# board.net
KiCad netlist of a schematic drawn in EAGLE
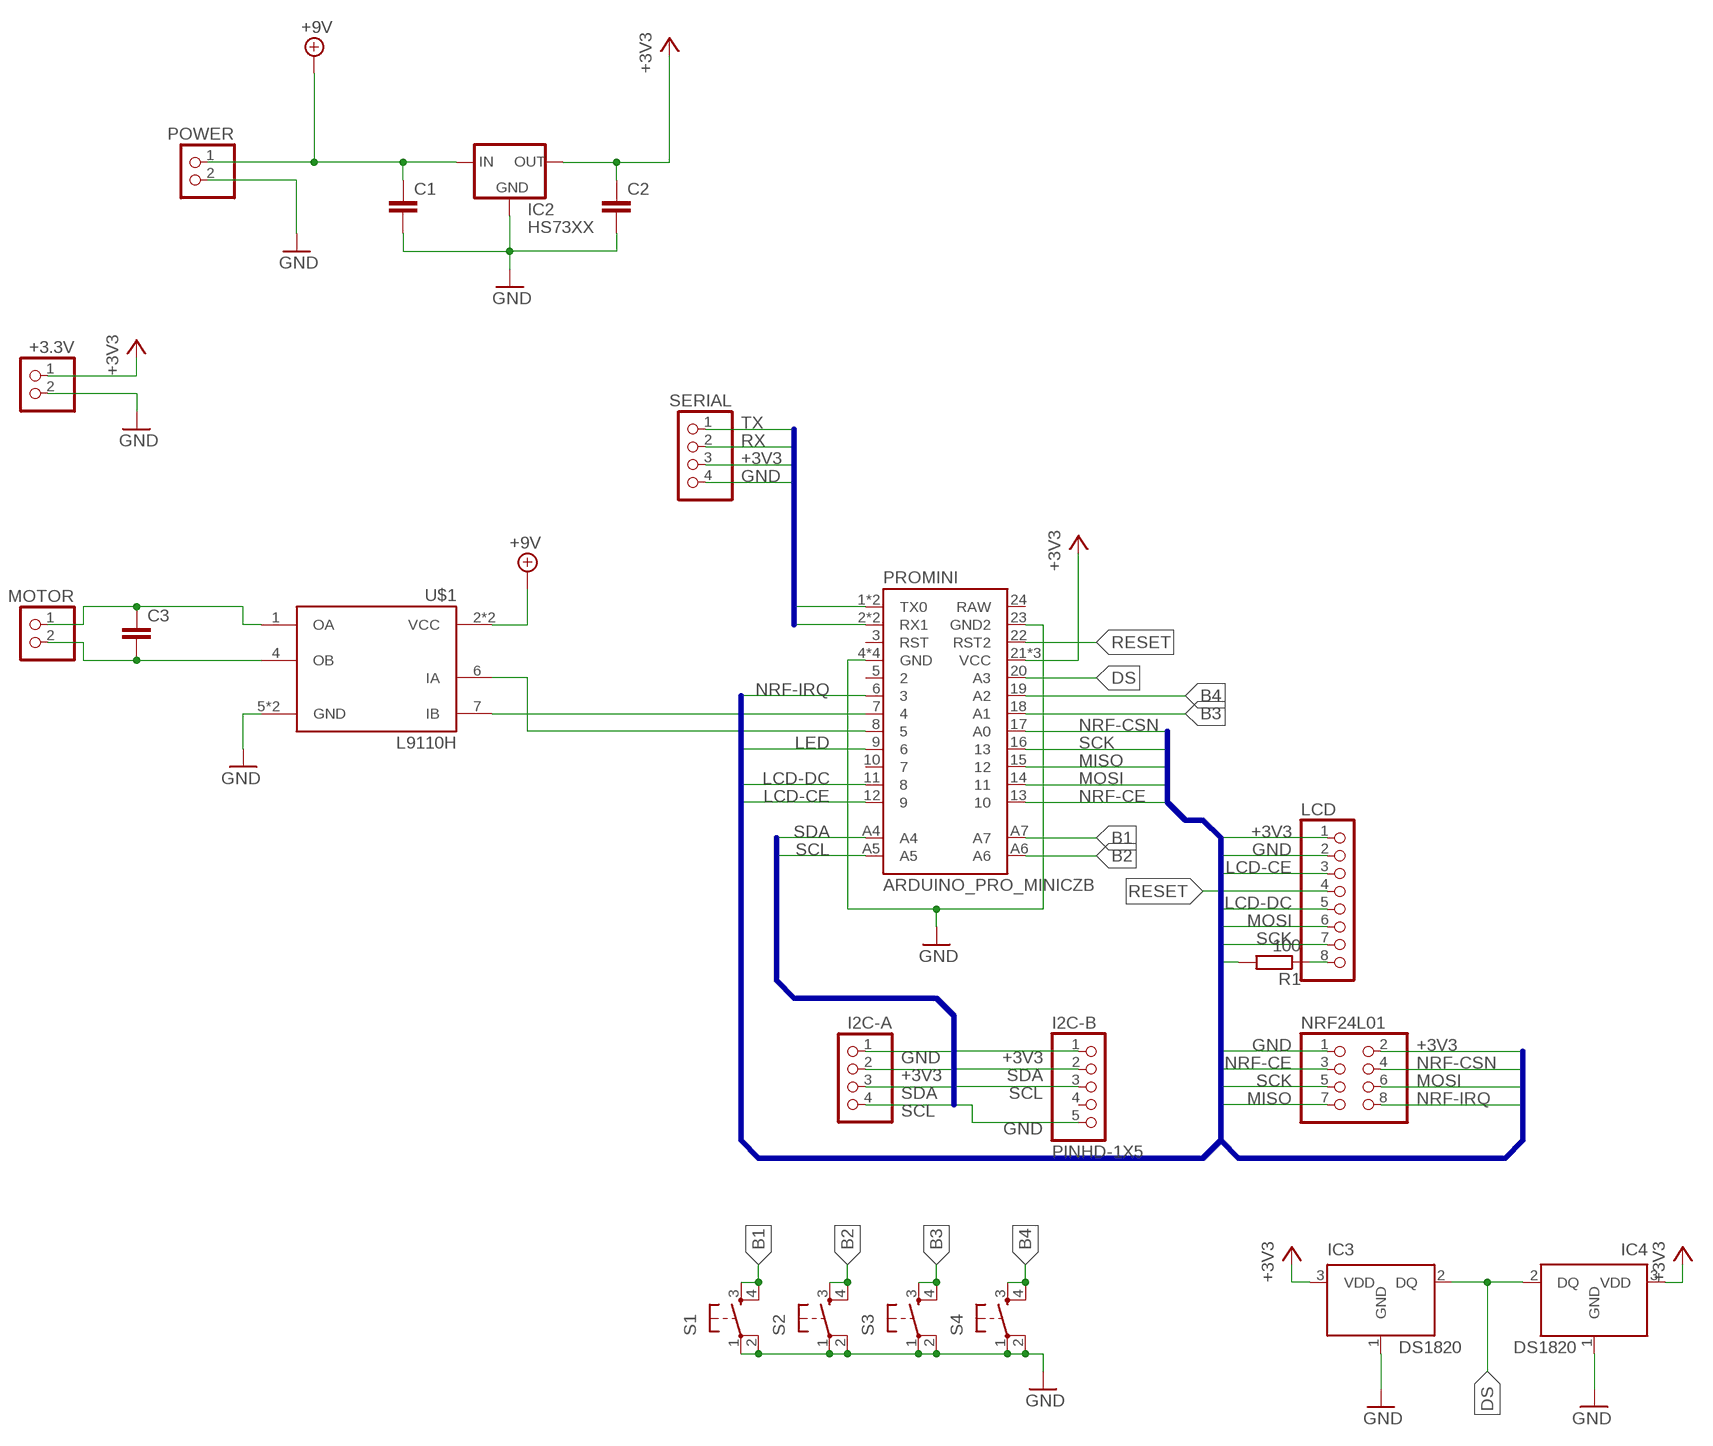
[diagram p0: schematic, sheet 1]

(export (version "E")
  (design (tool "Eeschema 10.0.6"))
  (components
    (comp (ref "+3.3V")
      (value "PINHD-1X2")
      (footprint "eagle-import:1X02")
      (libsource (lib "eagle-import") (part "PINHD-1X2"))
    )
    (comp (ref "C1")
      (value "C-EU025-024X044")
      (footprint "eagle-import:C025-024X044")
      (libsource (lib "eagle-import") (part "C-EU025-024X044"))
    )
    (comp (ref "C2")
      (value "C-EU025-024X044")
      (footprint "eagle-import:C025-024X044")
      (libsource (lib "eagle-import") (part "C-EU025-024X044"))
    )
    (comp (ref "C3")
      (value "C-EU025-024X044")
      (footprint "eagle-import:C025-024X044")
      (libsource (lib "eagle-import") (part "C-EU025-024X044"))
    )
    (comp (ref "I2C-A")
      (value "PINHD-1X4")
      (footprint "eagle-import:1X04")
      (libsource (lib "eagle-import") (part "PINHD-1X4"))
    )
    (comp (ref "I2C-B")
      (value "PINHD-1X5")
      (footprint "eagle-import:1X05")
      (libsource (lib "eagle-import") (part "PINHD-1X5"))
    )
    (comp (ref "IC2")
      (value "HS73XX")
      (footprint "eagle-import:TO92")
      (libsource (lib "eagle-import") (part "HS73XX"))
    )
    (comp (ref "IC3")
      (value "DS1820")
      (footprint "eagle-import:TO-92")
      (libsource (lib "eagle-import") (part "DS1820"))
    )
    (comp (ref "IC4")
      (value "DS1820")
      (footprint "eagle-import:TO-92")
      (libsource (lib "eagle-import") (part "DS1820"))
    )
    (comp (ref "LCD")
      (value "PINHD-1X8")
      (footprint "eagle-import:1X08")
      (libsource (lib "eagle-import") (part "PINHD-1X8"))
    )
    (comp (ref "MOTOR")
      (value "PINHD-1X2")
      (footprint "eagle-import:1X02")
      (libsource (lib "eagle-import") (part "PINHD-1X2"))
    )
    (comp (ref "NRF24L01")
      (value "PINHD-2X4")
      (footprint "eagle-import:2X04")
      (libsource (lib "eagle-import") (part "PINHD-2X4"))
    )
    (comp (ref "POWER")
      (value "PINHD-1X2")
      (footprint "eagle-import:1X02")
      (libsource (lib "eagle-import") (part "PINHD-1X2"))
    )
    (comp (ref "PROMINI")
      (value "ARDUINO_PRO_MINICZB")
      (footprint "eagle-import:PRO_MINI_2")
      (libsource (lib "eagle-import") (part "ARDUINO_PRO_MINICZB"))
    )
    (comp (ref "R1")
      (value "100")
      (footprint "eagle-import:0204_7")
      (libsource (lib "eagle-import") (part "R-EU_0204/7"))
    )
    (comp (ref "S1")
      (value "TAC_SWITCHPTH")
      (footprint "eagle-import:TACTILE-PTH")
      (libsource (lib "eagle-import") (part "TAC_SWITCHPTH"))
    )
    (comp (ref "S2")
      (value "TAC_SWITCHPTH")
      (footprint "eagle-import:TACTILE-PTH")
      (libsource (lib "eagle-import") (part "TAC_SWITCHPTH"))
    )
    (comp (ref "S3")
      (value "TAC_SWITCHPTH")
      (footprint "eagle-import:TACTILE-PTH")
      (libsource (lib "eagle-import") (part "TAC_SWITCHPTH"))
    )
    (comp (ref "S4")
      (value "TAC_SWITCHPTH")
      (footprint "eagle-import:TACTILE-PTH")
      (libsource (lib "eagle-import") (part "TAC_SWITCHPTH"))
    )
    (comp (ref "SERIAL")
      (value "PINHD-1X4")
      (footprint "eagle-import:1X04")
      (libsource (lib "eagle-import") (part "PINHD-1X4"))
    )
    (comp (ref "U$1")
      (value "L9110H")
      (footprint "eagle-import:DIL08")
      (libsource (lib "eagle-import") (part "L9110H"))
    )
  )
  (nets
    (net (code "1") (name "+3V3") (class "Default")
      (node (ref "+3.3V") (pin "1") (pinfunction "1_1") (pintype "passive"))
      (node (ref "C2") (pin "1") (pinfunction "1_1") (pintype "passive"))
      (node (ref "I2C-A") (pin "2") (pinfunction "2_2") (pintype "passive"))
      (node (ref "I2C-B") (pin "1") (pinfunction "1_1") (pintype "passive"))
      (node (ref "IC2") (pin "3") (pinfunction "OUT_3") (pintype "passive"))
      (node (ref "IC3") (pin "3") (pinfunction "VDD_3") (pintype "input"))
      (node (ref "IC4") (pin "3") (pinfunction "VDD_3") (pintype "input"))
      (node (ref "LCD") (pin "1") (pinfunction "1_1") (pintype "passive"))
      (node (ref "NRF24L01") (pin "2") (pinfunction "2_2") (pintype "passive"))
      (node (ref "PROMINI") (pin "21") (pinfunction "VCC_21") (pintype "bidirectional"))
      (node (ref "PROMINI") (pin "V") (pinfunction "VCC_V") (pintype "bidirectional"))
      (node (ref "PROMINI") (pin "VCC") (pinfunction "VCC_VCC") (pintype "bidirectional"))
      (node (ref "SERIAL") (pin "3") (pinfunction "3_3") (pintype "passive"))
    )
    (net (code "2") (name "+9V") (class "Default")
      (node (ref "C1") (pin "1") (pinfunction "1_1") (pintype "passive"))
      (node (ref "IC2") (pin "2") (pinfunction "IN_2") (pintype "input"))
      (node (ref "POWER") (pin "1") (pinfunction "1_1") (pintype "passive"))
      (node (ref "U$1") (pin "2") (pinfunction "VCC_2") (pintype "power_in"))
      (node (ref "U$1") (pin "3") (pinfunction "VCC_3") (pintype "power_in"))
    )
    (net (code "3") (name "/LCD-CE") (class "Default")
      (node (ref "LCD") (pin "3") (pinfunction "3_3") (pintype "passive"))
      (node (ref "PROMINI") (pin "12") (pinfunction "9_12") (pintype "bidirectional"))
    )
    (net (code "4") (name "/LCD-DC") (class "Default")
      (node (ref "LCD") (pin "5") (pinfunction "5_5") (pintype "passive"))
      (node (ref "PROMINI") (pin "11") (pinfunction "8_11") (pintype "bidirectional"))
    )
    (net (code "5") (name "/LED") (class "Default")
      (node (ref "PROMINI") (pin "9") (pinfunction "6_9") (pintype "bidirectional"))
      (node (ref "R1") (pin "2") (pinfunction "2_2") (pintype "passive"))
    )
    (net (code "6") (name "/MISO") (class "Default")
      (node (ref "NRF24L01") (pin "7") (pinfunction "7_7") (pintype "passive"))
      (node (ref "PROMINI") (pin "15") (pinfunction "12_15") (pintype "bidirectional"))
    )
    (net (code "7") (name "/MOSI") (class "Default")
      (node (ref "LCD") (pin "6") (pinfunction "6_6") (pintype "passive"))
      (node (ref "NRF24L01") (pin "6") (pinfunction "6_6") (pintype "passive"))
      (node (ref "PROMINI") (pin "14") (pinfunction "11_14") (pintype "bidirectional"))
    )
    (net (code "8") (name "/NRF-CE") (class "Default")
      (node (ref "NRF24L01") (pin "3") (pinfunction "3_3") (pintype "passive"))
      (node (ref "PROMINI") (pin "13") (pinfunction "10_13") (pintype "bidirectional"))
    )
    (net (code "9") (name "/NRF-CSN") (class "Default")
      (node (ref "NRF24L01") (pin "4") (pinfunction "4_4") (pintype "passive"))
      (node (ref "PROMINI") (pin "17") (pinfunction "A0_17") (pintype "bidirectional"))
    )
    (net (code "10") (name "/NRF-IRQ") (class "Default")
      (node (ref "NRF24L01") (pin "8") (pinfunction "8_8") (pintype "passive"))
      (node (ref "PROMINI") (pin "6") (pinfunction "3_6") (pintype "bidirectional"))
    )
    (net (code "11") (name "/RX") (class "Default")
      (node (ref "PROMINI") (pin "2") (pinfunction "RX1_2") (pintype "bidirectional"))
      (node (ref "PROMINI") (pin "RXI") (pinfunction "RX1_RXI") (pintype "bidirectional"))
      (node (ref "SERIAL") (pin "2") (pinfunction "2_2") (pintype "passive"))
    )
    (net (code "12") (name "/SCK") (class "Default")
      (node (ref "LCD") (pin "7") (pinfunction "7_7") (pintype "passive"))
      (node (ref "NRF24L01") (pin "5") (pinfunction "5_5") (pintype "passive"))
      (node (ref "PROMINI") (pin "16") (pinfunction "13_16") (pintype "bidirectional"))
    )
    (net (code "13") (name "/SCL") (class "Default")
      (node (ref "I2C-A") (pin "4") (pinfunction "4_4") (pintype "passive"))
      (node (ref "I2C-B") (pin "3") (pinfunction "3_3") (pintype "passive"))
      (node (ref "PROMINI") (pin "A5") (pinfunction "A5_A5") (pintype "bidirectional"))
    )
    (net (code "14") (name "/SDA") (class "Default")
      (node (ref "I2C-A") (pin "3") (pinfunction "3_3") (pintype "passive"))
      (node (ref "I2C-B") (pin "2") (pinfunction "2_2") (pintype "passive"))
      (node (ref "PROMINI") (pin "A4") (pinfunction "A4_A4") (pintype "bidirectional"))
    )
    (net (code "15") (name "/TX") (class "Default")
      (node (ref "PROMINI") (pin "1") (pinfunction "TX0_1") (pintype "bidirectional"))
      (node (ref "PROMINI") (pin "TXO") (pinfunction "TX0_TXO") (pintype "bidirectional"))
      (node (ref "SERIAL") (pin "1") (pinfunction "1_1") (pintype "passive"))
    )
    (net (code "16") (name "B1") (class "Default")
      (node (ref "PROMINI") (pin "A7") (pinfunction "A7_A7") (pintype "bidirectional"))
      (node (ref "S1") (pin "3") (pinfunction "3_3") (pintype "passive"))
      (node (ref "S1") (pin "4") (pinfunction "4_4") (pintype "passive"))
    )
    (net (code "17") (name "B2") (class "Default")
      (node (ref "PROMINI") (pin "A6") (pinfunction "A6_A6") (pintype "bidirectional"))
      (node (ref "S2") (pin "3") (pinfunction "3_3") (pintype "passive"))
      (node (ref "S2") (pin "4") (pinfunction "4_4") (pintype "passive"))
    )
    (net (code "18") (name "B3") (class "Default")
      (node (ref "PROMINI") (pin "18") (pinfunction "A1_18") (pintype "bidirectional"))
      (node (ref "S3") (pin "3") (pinfunction "3_3") (pintype "passive"))
      (node (ref "S3") (pin "4") (pinfunction "4_4") (pintype "passive"))
    )
    (net (code "19") (name "B4") (class "Default")
      (node (ref "PROMINI") (pin "19") (pinfunction "A2_19") (pintype "bidirectional"))
      (node (ref "S4") (pin "3") (pinfunction "3_3") (pintype "passive"))
      (node (ref "S4") (pin "4") (pinfunction "4_4") (pintype "passive"))
    )
    (net (code "20") (name "DS") (class "Default")
      (node (ref "IC3") (pin "2") (pinfunction "DQ_2") (pintype "output"))
      (node (ref "IC4") (pin "2") (pinfunction "DQ_2") (pintype "output"))
      (node (ref "PROMINI") (pin "20") (pinfunction "A3_20") (pintype "bidirectional"))
    )
    (net (code "21") (name "GND") (class "Default")
      (node (ref "+3.3V") (pin "2") (pinfunction "2_2") (pintype "passive"))
      (node (ref "C1") (pin "2") (pinfunction "2_2") (pintype "passive"))
      (node (ref "C2") (pin "2") (pinfunction "2_2") (pintype "passive"))
      (node (ref "I2C-A") (pin "1") (pinfunction "1_1") (pintype "passive"))
      (node (ref "I2C-B") (pin "5") (pinfunction "5_5") (pintype "passive"))
      (node (ref "IC2") (pin "1") (pinfunction "GND_1") (pintype "input"))
      (node (ref "IC3") (pin "1") (pinfunction "GND_1") (pintype "power_in"))
      (node (ref "IC4") (pin "1") (pinfunction "GND_1") (pintype "power_in"))
      (node (ref "LCD") (pin "2") (pinfunction "2_2") (pintype "passive"))
      (node (ref "NRF24L01") (pin "1") (pinfunction "1_1") (pintype "passive"))
      (node (ref "POWER") (pin "2") (pinfunction "2_2") (pintype "passive"))
      (node (ref "PROMINI") (pin "23") (pinfunction "GND2_23") (pintype "bidirectional"))
      (node (ref "PROMINI") (pin "4") (pinfunction "GND_4") (pintype "bidirectional"))
      (node (ref "PROMINI") (pin "BLK") (pinfunction "GND_BLK") (pintype "bidirectional"))
      (node (ref "PROMINI") (pin "G") (pinfunction "GND_G") (pintype "bidirectional"))
      (node (ref "PROMINI") (pin "GND") (pinfunction "GND_GND") (pintype "bidirectional"))
      (node (ref "S1") (pin "1") (pinfunction "1_1") (pintype "passive"))
      (node (ref "S1") (pin "2") (pinfunction "2_2") (pintype "passive"))
      (node (ref "S2") (pin "1") (pinfunction "1_1") (pintype "passive"))
      (node (ref "S2") (pin "2") (pinfunction "2_2") (pintype "passive"))
      (node (ref "S3") (pin "1") (pinfunction "1_1") (pintype "passive"))
      (node (ref "S3") (pin "2") (pinfunction "2_2") (pintype "passive"))
      (node (ref "S4") (pin "1") (pinfunction "1_1") (pintype "passive"))
      (node (ref "S4") (pin "2") (pinfunction "2_2") (pintype "passive"))
      (node (ref "SERIAL") (pin "4") (pinfunction "4_4") (pintype "passive"))
      (node (ref "U$1") (pin "5") (pinfunction "GND_5") (pintype "power_in"))
      (node (ref "U$1") (pin "8") (pinfunction "GND_8") (pintype "power_in"))
    )
    (net (code "22") (name "Net-(LCD-Pad8)") (class "Default")
      (node (ref "LCD") (pin "8") (pinfunction "8_8") (pintype "passive"))
      (node (ref "R1") (pin "1") (pinfunction "1_1") (pintype "passive"))
    )
    (net (code "23") (name "Net-(PROMINI-4)") (class "Default")
      (node (ref "PROMINI") (pin "7") (pinfunction "4_7") (pintype "bidirectional"))
      (node (ref "U$1") (pin "7") (pinfunction "IB_7") (pintype "bidirectional"))
    )
    (net (code "24") (name "Net-(PROMINI-5)") (class "Default")
      (node (ref "PROMINI") (pin "8") (pinfunction "5_8") (pintype "bidirectional"))
      (node (ref "U$1") (pin "6") (pinfunction "IA_6") (pintype "bidirectional"))
    )
    (net (code "25") (name "Net-(U$1-OA)") (class "Default")
      (node (ref "C3") (pin "1") (pinfunction "1_1") (pintype "passive"))
      (node (ref "MOTOR") (pin "1") (pinfunction "1_1") (pintype "passive"))
      (node (ref "U$1") (pin "1") (pinfunction "OA_1") (pintype "bidirectional"))
    )
    (net (code "26") (name "Net-(U$1-OB)") (class "Default")
      (node (ref "C3") (pin "2") (pinfunction "2_2") (pintype "passive"))
      (node (ref "MOTOR") (pin "2") (pinfunction "2_2") (pintype "passive"))
      (node (ref "U$1") (pin "4") (pinfunction "OB_4") (pintype "bidirectional"))
    )
    (net (code "27") (name "RESET") (class "Default")
      (node (ref "LCD") (pin "4") (pinfunction "4_4") (pintype "passive"))
      (node (ref "PROMINI") (pin "22") (pinfunction "RST2_22") (pintype "bidirectional"))
    )
    (net (code "28") (name "unconnected-(I2C-B-Pad4)") (class "Default")
      (node (ref "I2C-B") (pin "4") (pinfunction "4_4") (pintype "passive"))
    )
    (net (code "29") (name "unconnected-(PROMINI-2-Pad5)") (class "Default")
      (node (ref "PROMINI") (pin "5") (pinfunction "2_5") (pintype "bidirectional"))
    )
    (net (code "30") (name "unconnected-(PROMINI-7-Pad10)") (class "Default")
      (node (ref "PROMINI") (pin "10") (pinfunction "7_10") (pintype "bidirectional"))
    )
    (net (code "31") (name "unconnected-(PROMINI-RAW-Pad24)") (class "Default")
      (node (ref "PROMINI") (pin "24") (pinfunction "RAW_24") (pintype "bidirectional"))
    )
    (net (code "32") (name "unconnected-(PROMINI-RST-Pad3)") (class "Default")
      (node (ref "PROMINI") (pin "3") (pinfunction "RST_3") (pintype "bidirectional"))
    )
  )
)
